# MyOrthotic_2_0000.net
KiCad netlist of a schematic drawn in EAGLE
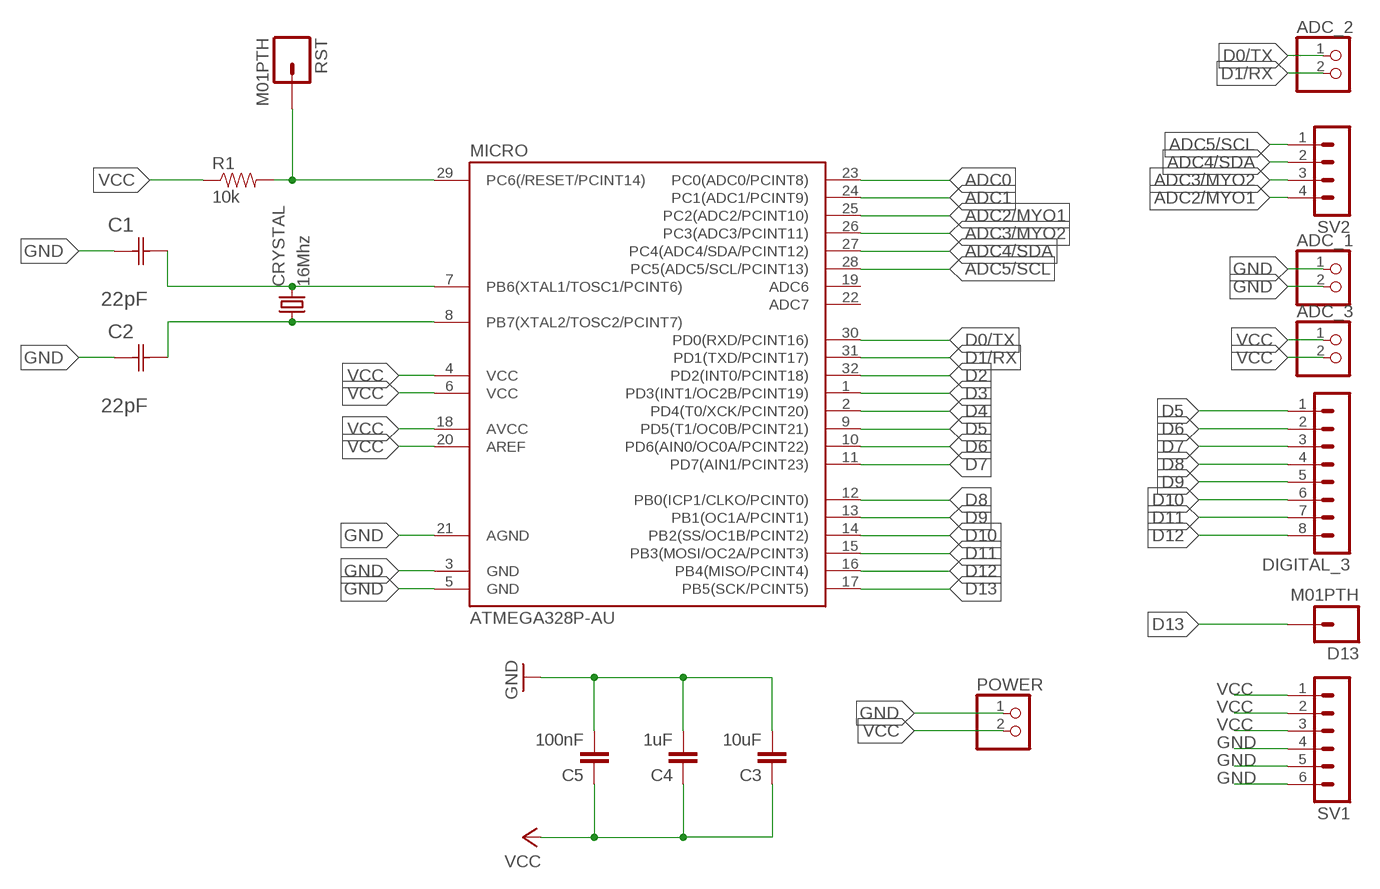
[diagram p0: schematic, sheet 1]

(export (version "E")
  (design (tool "Eeschema 10.0.6"))
  (components
    (comp (ref "ADC_1")
      (value "PINHD-1X2")
      (footprint "eagle-import:1X02")
      (libsource (lib "eagle-import") (part "PINHD-1X2"))
    )
    (comp (ref "ADC_2")
      (value "PINHD-1X2")
      (footprint "eagle-import:1X02")
      (libsource (lib "eagle-import") (part "PINHD-1X2"))
    )
    (comp (ref "ADC_3")
      (value "PINHD-1X2")
      (footprint "eagle-import:1X02")
      (libsource (lib "eagle-import") (part "PINHD-1X2"))
    )
    (comp (ref "C1")
      (value "22pF")
      (footprint "eagle-import:CAPC3216X178N")
      (fields (field (name "MPN") "0612ZC225MAT2A") (field (name "TOLERANCE") "±20%"))
      (libsource (lib "eagle-import") (part "0612ZC225MAT2A"))
    )
    (comp (ref "C2")
      (value "22pF")
      (footprint "eagle-import:CAPC3216X178N")
      (fields (field (name "MPN") "0612ZC225MAT2A") (field (name "TOLERANCE") "±20%"))
      (libsource (lib "eagle-import") (part "0612ZC225MAT2A"))
    )
    (comp (ref "C3")
      (value "10uF")
      (footprint "eagle-import:1206")
      (libsource (lib "eagle-import") (part "CAP1206"))
    )
    (comp (ref "C4")
      (value "1uF")
      (footprint "eagle-import:1206")
      (libsource (lib "eagle-import") (part "CAP1206"))
    )
    (comp (ref "C5")
      (value "100nF")
      (footprint "eagle-import:1206")
      (libsource (lib "eagle-import") (part "CAP1206"))
    )
    (comp (ref "CRYSTAL")
      (value "16Mhz")
      (footprint "eagle-import:CSM-7X-DU")
      (libsource (lib "eagle-import") (part "CSM-7X-DU"))
    )
    (comp (ref "D13")
      (value "M01PTH")
      (footprint "eagle-import:1X01")
      (libsource (lib "eagle-import") (part "M01PTH"))
    )
    (comp (ref "DIGITAL_3")
      (value "MA08-1")
      (footprint "eagle-import:MA08-1")
      (libsource (lib "eagle-import") (part "MA08-1"))
    )
    (comp (ref "MICRO")
      (value "ATMEGA328P-AU")
      (footprint "eagle-import:TQFP32-08")
      (libsource (lib "eagle-import") (part "ATMEGA48/88/168-AU"))
    )
    (comp (ref "POWER")
      (value "PINHD-1X2")
      (footprint "eagle-import:1X02")
      (libsource (lib "eagle-import") (part "PINHD-1X2"))
    )
    (comp (ref "R1")
      (value "10k")
      (footprint "eagle-import:1206")
      (libsource (lib "eagle-import") (part "RESISTOR1206"))
    )
    (comp (ref "RST")
      (value "M01PTH")
      (footprint "eagle-import:1X01")
      (libsource (lib "eagle-import") (part "M01PTH"))
    )
    (comp (ref "SV1")
      (value "MA06-1")
      (footprint "eagle-import:MA06-1")
      (libsource (lib "eagle-import") (part "MA06-1"))
    )
    (comp (ref "SV2")
      (value "MA04-1")
      (footprint "eagle-import:MA04-1")
      (libsource (lib "eagle-import") (part "MA04-1"))
    )
  )
  (nets
    (net (code "1") (name "ADC0") (class "Default")
      (node (ref "MICRO") (pin "23") (pinfunction "PC0(ADC0/PCINT8)_23") (pintype "bidirectional"))
    )
    (net (code "2") (name "ADC1") (class "Default")
      (node (ref "MICRO") (pin "24") (pinfunction "PC1(ADC1/PCINT9)_24") (pintype "bidirectional"))
    )
    (net (code "3") (name "ADC2{slash}MYO1") (class "Default")
      (node (ref "MICRO") (pin "25") (pinfunction "PC2(ADC2/PCINT10)_25") (pintype "bidirectional"))
      (node (ref "SV2") (pin "4") (pinfunction "4_4") (pintype "passive"))
    )
    (net (code "4") (name "ADC3{slash}MYO2") (class "Default")
      (node (ref "MICRO") (pin "26") (pinfunction "PC3(ADC3/PCINT11)_26") (pintype "bidirectional"))
      (node (ref "SV2") (pin "3") (pinfunction "3_3") (pintype "passive"))
    )
    (net (code "5") (name "ADC4{slash}SDA") (class "Default")
      (node (ref "MICRO") (pin "27") (pinfunction "PC4(ADC4/SDA/PCINT12)_27") (pintype "bidirectional"))
      (node (ref "SV2") (pin "2") (pinfunction "2_2") (pintype "passive"))
    )
    (net (code "6") (name "ADC5{slash}SCL") (class "Default")
      (node (ref "MICRO") (pin "28") (pinfunction "PC5(ADC5/SCL/PCINT13)_28") (pintype "bidirectional"))
      (node (ref "SV2") (pin "1") (pinfunction "1_1") (pintype "passive"))
    )
    (net (code "7") (name "D0{slash}TX") (class "Default")
      (node (ref "ADC_2") (pin "1") (pinfunction "1_1") (pintype "passive"))
      (node (ref "MICRO") (pin "30") (pinfunction "PD0(RXD/PCINT16)_30") (pintype "bidirectional"))
    )
    (net (code "8") (name "D1{slash}RX") (class "Default")
      (node (ref "ADC_2") (pin "2") (pinfunction "2_2") (pintype "passive"))
      (node (ref "MICRO") (pin "31") (pinfunction "PD1(TXD/PCINT17)_31") (pintype "bidirectional"))
    )
    (net (code "9") (name "D2") (class "Default")
      (node (ref "MICRO") (pin "32") (pinfunction "PD2(INT0/PCINT18)_32") (pintype "bidirectional"))
    )
    (net (code "10") (name "D3") (class "Default")
      (node (ref "MICRO") (pin "1") (pinfunction "PD3(INT1/OC2B/PCINT19)_1") (pintype "bidirectional"))
    )
    (net (code "11") (name "D4") (class "Default")
      (node (ref "MICRO") (pin "2") (pinfunction "PD4(T0/XCK/PCINT20)_2") (pintype "bidirectional"))
    )
    (net (code "12") (name "D5") (class "Default")
      (node (ref "DIGITAL_3") (pin "1") (pinfunction "1_1") (pintype "passive"))
      (node (ref "MICRO") (pin "9") (pinfunction "PD5(T1/OC0B/PCINT21)_9") (pintype "bidirectional"))
    )
    (net (code "13") (name "D6") (class "Default")
      (node (ref "DIGITAL_3") (pin "2") (pinfunction "2_2") (pintype "passive"))
      (node (ref "MICRO") (pin "10") (pinfunction "PD6(AIN0/OC0A/PCINT22)_10") (pintype "bidirectional"))
    )
    (net (code "14") (name "D7") (class "Default")
      (node (ref "DIGITAL_3") (pin "3") (pinfunction "3_3") (pintype "passive"))
      (node (ref "MICRO") (pin "11") (pinfunction "PD7(AIN1/PCINT23)_11") (pintype "bidirectional"))
    )
    (net (code "15") (name "D8") (class "Default")
      (node (ref "DIGITAL_3") (pin "4") (pinfunction "4_4") (pintype "passive"))
      (node (ref "MICRO") (pin "12") (pinfunction "PB0(ICP1/CLKO/PCINT0)_12") (pintype "bidirectional"))
    )
    (net (code "16") (name "D9") (class "Default")
      (node (ref "DIGITAL_3") (pin "5") (pinfunction "5_5") (pintype "passive"))
      (node (ref "MICRO") (pin "13") (pinfunction "PB1(OC1A/PCINT1)_13") (pintype "bidirectional"))
    )
    (net (code "17") (name "D10") (class "Default")
      (node (ref "DIGITAL_3") (pin "6") (pinfunction "6_6") (pintype "passive"))
      (node (ref "MICRO") (pin "14") (pinfunction "PB2(SS/OC1B/PCINT2)_14") (pintype "bidirectional"))
    )
    (net (code "18") (name "D11") (class "Default")
      (node (ref "DIGITAL_3") (pin "7") (pinfunction "7_7") (pintype "passive"))
      (node (ref "MICRO") (pin "15") (pinfunction "PB3(MOSI/OC2A/PCINT3)_15") (pintype "bidirectional"))
    )
    (net (code "19") (name "D12") (class "Default")
      (node (ref "DIGITAL_3") (pin "8") (pinfunction "8_8") (pintype "passive"))
      (node (ref "MICRO") (pin "16") (pinfunction "PB4(MISO/PCINT4)_16") (pintype "bidirectional"))
    )
    (net (code "20") (name "D13") (class "Default")
      (node (ref "D13") (pin "1") (pinfunction "1_1") (pintype "passive"))
      (node (ref "MICRO") (pin "17") (pinfunction "PB5(SCK/PCINT5)_17") (pintype "bidirectional"))
    )
    (net (code "21") (name "GND") (class "Default")
      (node (ref "ADC_1") (pin "1") (pinfunction "1_1") (pintype "passive"))
      (node (ref "ADC_1") (pin "2") (pinfunction "2_2") (pintype "passive"))
      (node (ref "C1") (pin "1") (pinfunction "C1_1") (pintype "passive"))
      (node (ref "C2") (pin "1") (pinfunction "C1_1") (pintype "passive"))
      (node (ref "C3") (pin "2") (pinfunction "2_2") (pintype "passive"))
      (node (ref "C4") (pin "2") (pinfunction "2_2") (pintype "passive"))
      (node (ref "C5") (pin "2") (pinfunction "2_2") (pintype "passive"))
      (node (ref "MICRO") (pin "21") (pinfunction "AGND_21") (pintype "power_in"))
      (node (ref "MICRO") (pin "3") (pinfunction "GND_3") (pintype "power_in"))
      (node (ref "MICRO") (pin "5") (pinfunction "GND_5") (pintype "power_in"))
      (node (ref "POWER") (pin "1") (pinfunction "1_1") (pintype "passive"))
      (node (ref "SV1") (pin "4") (pinfunction "4_4") (pintype "passive"))
      (node (ref "SV1") (pin "5") (pinfunction "5_5") (pintype "passive"))
      (node (ref "SV1") (pin "6") (pinfunction "6_6") (pintype "passive"))
    )
    (net (code "22") (name "Net-(C1-C2)") (class "Default")
      (node (ref "C1") (pin "2") (pinfunction "C2_2") (pintype "passive"))
      (node (ref "CRYSTAL") (pin "2") (pinfunction "2_2") (pintype "passive"))
      (node (ref "MICRO") (pin "7") (pinfunction "PB6(XTAL1/TOSC1/PCINT6)_7") (pintype "bidirectional"))
    )
    (net (code "23") (name "Net-(C2-C2)") (class "Default")
      (node (ref "C2") (pin "2") (pinfunction "C2_2") (pintype "passive"))
      (node (ref "CRYSTAL") (pin "1") (pinfunction "1_1") (pintype "passive"))
      (node (ref "MICRO") (pin "8") (pinfunction "PB7(XTAL2/TOSC2/PCINT7)_8") (pintype "bidirectional"))
    )
    (net (code "24") (name "Net-(MICRO-PC6({slash}RESET{slash}PCINT14))") (class "Default")
      (node (ref "MICRO") (pin "29") (pinfunction "PC6(/RESET/PCINT14)_29") (pintype "bidirectional"))
      (node (ref "R1") (pin "2") (pinfunction "2_2") (pintype "passive"))
      (node (ref "RST") (pin "1") (pinfunction "1_1") (pintype "passive"))
    )
    (net (code "25") (name "VCC") (class "Default")
      (node (ref "ADC_3") (pin "1") (pinfunction "1_1") (pintype "passive"))
      (node (ref "ADC_3") (pin "2") (pinfunction "2_2") (pintype "passive"))
      (node (ref "C3") (pin "1") (pinfunction "1_1") (pintype "passive"))
      (node (ref "C4") (pin "1") (pinfunction "1_1") (pintype "passive"))
      (node (ref "C5") (pin "1") (pinfunction "1_1") (pintype "passive"))
      (node (ref "MICRO") (pin "18") (pinfunction "AVCC_18") (pintype "passive"))
      (node (ref "MICRO") (pin "20") (pinfunction "AREF_20") (pintype "passive"))
      (node (ref "MICRO") (pin "4") (pinfunction "VCC_4") (pintype "power_in"))
      (node (ref "MICRO") (pin "6") (pinfunction "VCC_6") (pintype "power_in"))
      (node (ref "POWER") (pin "2") (pinfunction "2_2") (pintype "passive"))
      (node (ref "R1") (pin "1") (pinfunction "1_1") (pintype "passive"))
      (node (ref "SV1") (pin "1") (pinfunction "1_1") (pintype "passive"))
      (node (ref "SV1") (pin "2") (pinfunction "2_2") (pintype "passive"))
      (node (ref "SV1") (pin "3") (pinfunction "3_3") (pintype "passive"))
    )
    (net (code "26") (name "unconnected-(MICRO-ADC6-Pad19)") (class "Default")
      (node (ref "MICRO") (pin "19") (pinfunction "ADC6_19") (pintype "passive"))
    )
    (net (code "27") (name "unconnected-(MICRO-ADC7-Pad22)") (class "Default")
      (node (ref "MICRO") (pin "22") (pinfunction "ADC7_22") (pintype "passive"))
    )
  )
)
